# panel.net
KiCad netlist of a schematic drawn in Altium Designer
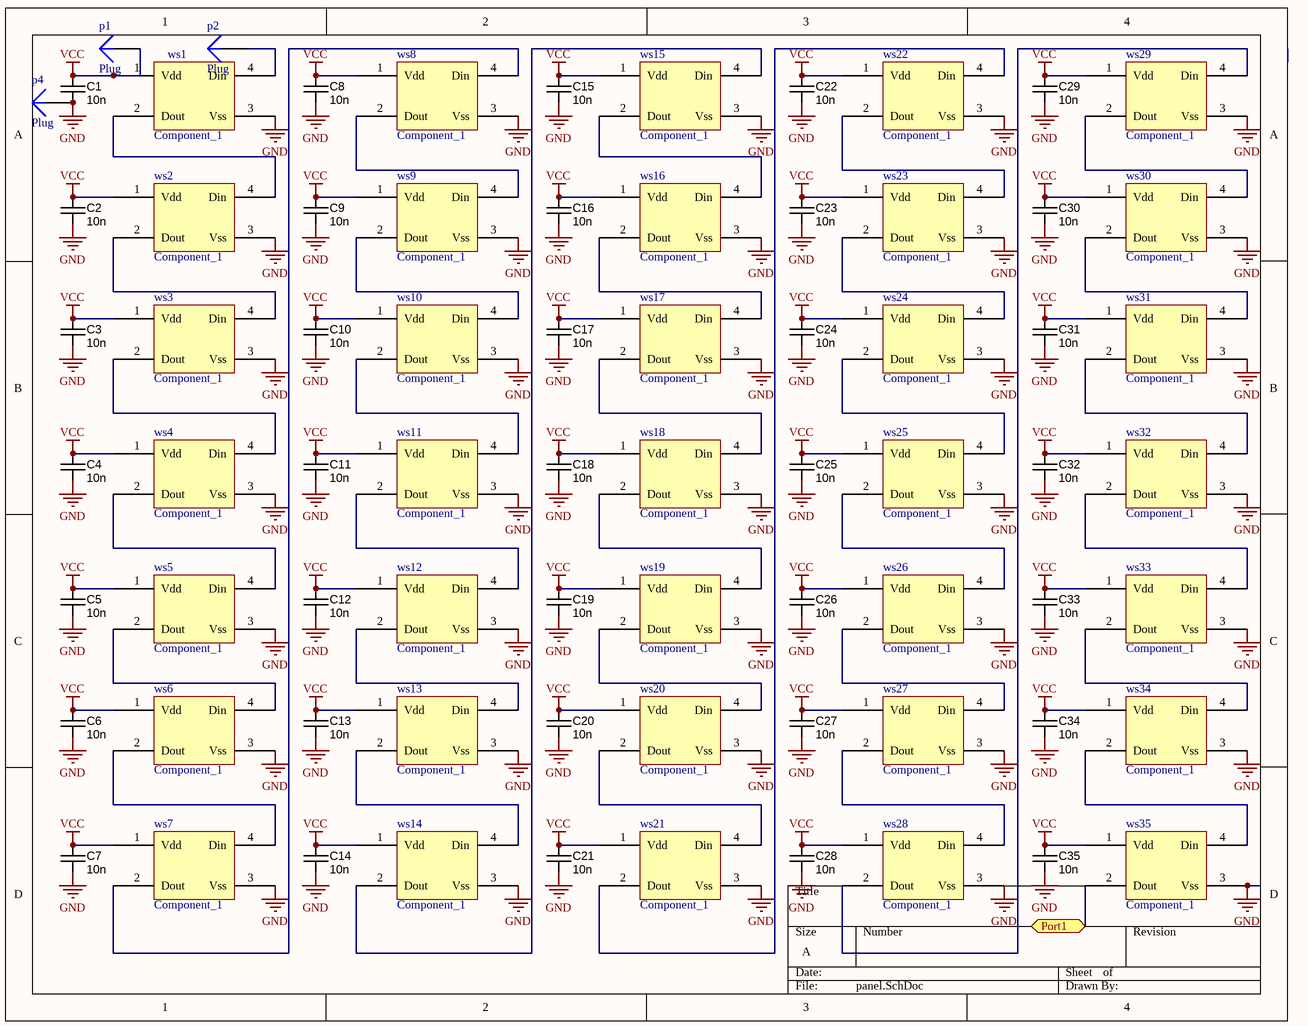
[diagram p0: panel.SchDoc]

(export (version "E")
  (design (tool "Eeschema 10.0.6"))
  (components
    (comp (ref "C1")
      (value "10n")
      (footprint "CAPC1608X90N")
      (description "Capacitor SMD Cer 10nF 10% 100V X7R 0603")
      (fields
        (field (name "TOLERANCE") "±10%")
        (field (name "MANUFACTURER") "Murata Electronics North America")
      )
      (libsource (lib "PBL - Capacitors") (part "CAPC_10n_0603_X7R_100V_10%"))
    )
    (comp (ref "C2")
      (value "10n")
      (footprint "CAPC1608X90N")
      (description "Capacitor SMD Cer 10nF 10% 100V X7R 0603")
      (fields
        (field (name "TOLERANCE") "±10%")
        (field (name "MANUFACTURER") "Murata Electronics North America")
      )
      (libsource (lib "PBL - Capacitors") (part "CAPC_10n_0603_X7R_100V_10%"))
    )
    (comp (ref "C3")
      (value "10n")
      (footprint "CAPC1608X90N")
      (description "Capacitor SMD Cer 10nF 10% 100V X7R 0603")
      (fields
        (field (name "TOLERANCE") "±10%")
        (field (name "MANUFACTURER") "Murata Electronics North America")
      )
      (libsource (lib "PBL - Capacitors") (part "CAPC_10n_0603_X7R_100V_10%"))
    )
    (comp (ref "C4")
      (value "10n")
      (footprint "CAPC1608X90N")
      (description "Capacitor SMD Cer 10nF 10% 100V X7R 0603")
      (fields
        (field (name "TOLERANCE") "±10%")
        (field (name "MANUFACTURER") "Murata Electronics North America")
      )
      (libsource (lib "PBL - Capacitors") (part "CAPC_10n_0603_X7R_100V_10%"))
    )
    (comp (ref "C5")
      (value "10n")
      (footprint "CAPC1608X90N")
      (description "Capacitor SMD Cer 10nF 10% 100V X7R 0603")
      (fields
        (field (name "TOLERANCE") "±10%")
        (field (name "MANUFACTURER") "Murata Electronics North America")
      )
      (libsource (lib "PBL - Capacitors") (part "CAPC_10n_0603_X7R_100V_10%"))
    )
    (comp (ref "C6")
      (value "10n")
      (footprint "CAPC1608X90N")
      (description "Capacitor SMD Cer 10nF 10% 100V X7R 0603")
      (fields
        (field (name "TOLERANCE") "±10%")
        (field (name "MANUFACTURER") "Murata Electronics North America")
      )
      (libsource (lib "PBL - Capacitors") (part "CAPC_10n_0603_X7R_100V_10%"))
    )
    (comp (ref "C7")
      (value "10n")
      (footprint "CAPC1608X90N")
      (description "Capacitor SMD Cer 10nF 10% 100V X7R 0603")
      (fields
        (field (name "TOLERANCE") "±10%")
        (field (name "MANUFACTURER") "Murata Electronics North America")
      )
      (libsource (lib "PBL - Capacitors") (part "CAPC_10n_0603_X7R_100V_10%"))
    )
    (comp (ref "C8")
      (value "10n")
      (footprint "CAPC1608X90N")
      (description "Capacitor SMD Cer 10nF 10% 100V X7R 0603")
      (fields
        (field (name "TOLERANCE") "±10%")
        (field (name "MANUFACTURER") "Murata Electronics North America")
      )
      (libsource (lib "PBL - Capacitors") (part "CAPC_10n_0603_X7R_100V_10%"))
    )
    (comp (ref "C9")
      (value "10n")
      (footprint "CAPC1608X90N")
      (description "Capacitor SMD Cer 10nF 10% 100V X7R 0603")
      (fields
        (field (name "TOLERANCE") "±10%")
        (field (name "MANUFACTURER") "Murata Electronics North America")
      )
      (libsource (lib "PBL - Capacitors") (part "CAPC_10n_0603_X7R_100V_10%"))
    )
    (comp (ref "C10")
      (value "10n")
      (footprint "CAPC1608X90N")
      (description "Capacitor SMD Cer 10nF 10% 100V X7R 0603")
      (fields
        (field (name "TOLERANCE") "±10%")
        (field (name "MANUFACTURER") "Murata Electronics North America")
      )
      (libsource (lib "PBL - Capacitors") (part "CAPC_10n_0603_X7R_100V_10%"))
    )
    (comp (ref "C11")
      (value "10n")
      (footprint "CAPC1608X90N")
      (description "Capacitor SMD Cer 10nF 10% 100V X7R 0603")
      (fields
        (field (name "TOLERANCE") "±10%")
        (field (name "MANUFACTURER") "Murata Electronics North America")
      )
      (libsource (lib "PBL - Capacitors") (part "CAPC_10n_0603_X7R_100V_10%"))
    )
    (comp (ref "C12")
      (value "10n")
      (footprint "CAPC1608X90N")
      (description "Capacitor SMD Cer 10nF 10% 100V X7R 0603")
      (fields
        (field (name "TOLERANCE") "±10%")
        (field (name "MANUFACTURER") "Murata Electronics North America")
      )
      (libsource (lib "PBL - Capacitors") (part "CAPC_10n_0603_X7R_100V_10%"))
    )
    (comp (ref "C13")
      (value "10n")
      (footprint "CAPC1608X90N")
      (description "Capacitor SMD Cer 10nF 10% 100V X7R 0603")
      (fields
        (field (name "TOLERANCE") "±10%")
        (field (name "MANUFACTURER") "Murata Electronics North America")
      )
      (libsource (lib "PBL - Capacitors") (part "CAPC_10n_0603_X7R_100V_10%"))
    )
    (comp (ref "C14")
      (value "10n")
      (footprint "CAPC1608X90N")
      (description "Capacitor SMD Cer 10nF 10% 100V X7R 0603")
      (fields
        (field (name "TOLERANCE") "±10%")
        (field (name "MANUFACTURER") "Murata Electronics North America")
      )
      (libsource (lib "PBL - Capacitors") (part "CAPC_10n_0603_X7R_100V_10%"))
    )
    (comp (ref "C15")
      (value "10n")
      (footprint "CAPC1608X90N")
      (description "Capacitor SMD Cer 10nF 10% 100V X7R 0603")
      (fields
        (field (name "TOLERANCE") "±10%")
        (field (name "MANUFACTURER") "Murata Electronics North America")
      )
      (libsource (lib "PBL - Capacitors") (part "CAPC_10n_0603_X7R_100V_10%"))
    )
    (comp (ref "C16")
      (value "10n")
      (footprint "CAPC1608X90N")
      (description "Capacitor SMD Cer 10nF 10% 100V X7R 0603")
      (fields
        (field (name "TOLERANCE") "±10%")
        (field (name "MANUFACTURER") "Murata Electronics North America")
      )
      (libsource (lib "PBL - Capacitors") (part "CAPC_10n_0603_X7R_100V_10%"))
    )
    (comp (ref "C17")
      (value "10n")
      (footprint "CAPC1608X90N")
      (description "Capacitor SMD Cer 10nF 10% 100V X7R 0603")
      (fields
        (field (name "TOLERANCE") "±10%")
        (field (name "MANUFACTURER") "Murata Electronics North America")
      )
      (libsource (lib "PBL - Capacitors") (part "CAPC_10n_0603_X7R_100V_10%"))
    )
    (comp (ref "C18")
      (value "10n")
      (footprint "CAPC1608X90N")
      (description "Capacitor SMD Cer 10nF 10% 100V X7R 0603")
      (fields
        (field (name "TOLERANCE") "±10%")
        (field (name "MANUFACTURER") "Murata Electronics North America")
      )
      (libsource (lib "PBL - Capacitors") (part "CAPC_10n_0603_X7R_100V_10%"))
    )
    (comp (ref "C19")
      (value "10n")
      (footprint "CAPC1608X90N")
      (description "Capacitor SMD Cer 10nF 10% 100V X7R 0603")
      (fields
        (field (name "TOLERANCE") "±10%")
        (field (name "MANUFACTURER") "Murata Electronics North America")
      )
      (libsource (lib "PBL - Capacitors") (part "CAPC_10n_0603_X7R_100V_10%"))
    )
    (comp (ref "C20")
      (value "10n")
      (footprint "CAPC1608X90N")
      (description "Capacitor SMD Cer 10nF 10% 100V X7R 0603")
      (fields
        (field (name "TOLERANCE") "±10%")
        (field (name "MANUFACTURER") "Murata Electronics North America")
      )
      (libsource (lib "PBL - Capacitors") (part "CAPC_10n_0603_X7R_100V_10%"))
    )
    (comp (ref "C21")
      (value "10n")
      (footprint "CAPC1608X90N")
      (description "Capacitor SMD Cer 10nF 10% 100V X7R 0603")
      (fields
        (field (name "TOLERANCE") "±10%")
        (field (name "MANUFACTURER") "Murata Electronics North America")
      )
      (libsource (lib "PBL - Capacitors") (part "CAPC_10n_0603_X7R_100V_10%"))
    )
    (comp (ref "C22")
      (value "10n")
      (footprint "CAPC1608X90N")
      (description "Capacitor SMD Cer 10nF 10% 100V X7R 0603")
      (fields
        (field (name "TOLERANCE") "±10%")
        (field (name "MANUFACTURER") "Murata Electronics North America")
      )
      (libsource (lib "PBL - Capacitors") (part "CAPC_10n_0603_X7R_100V_10%"))
    )
    (comp (ref "C23")
      (value "10n")
      (footprint "CAPC1608X90N")
      (description "Capacitor SMD Cer 10nF 10% 100V X7R 0603")
      (fields
        (field (name "TOLERANCE") "±10%")
        (field (name "MANUFACTURER") "Murata Electronics North America")
      )
      (libsource (lib "PBL - Capacitors") (part "CAPC_10n_0603_X7R_100V_10%"))
    )
    (comp (ref "C24")
      (value "10n")
      (footprint "CAPC1608X90N")
      (description "Capacitor SMD Cer 10nF 10% 100V X7R 0603")
      (fields
        (field (name "TOLERANCE") "±10%")
        (field (name "MANUFACTURER") "Murata Electronics North America")
      )
      (libsource (lib "PBL - Capacitors") (part "CAPC_10n_0603_X7R_100V_10%"))
    )
    (comp (ref "C25")
      (value "10n")
      (footprint "CAPC1608X90N")
      (description "Capacitor SMD Cer 10nF 10% 100V X7R 0603")
      (fields
        (field (name "TOLERANCE") "±10%")
        (field (name "MANUFACTURER") "Murata Electronics North America")
      )
      (libsource (lib "PBL - Capacitors") (part "CAPC_10n_0603_X7R_100V_10%"))
    )
    (comp (ref "C26")
      (value "10n")
      (footprint "CAPC1608X90N")
      (description "Capacitor SMD Cer 10nF 10% 100V X7R 0603")
      (fields
        (field (name "TOLERANCE") "±10%")
        (field (name "MANUFACTURER") "Murata Electronics North America")
      )
      (libsource (lib "PBL - Capacitors") (part "CAPC_10n_0603_X7R_100V_10%"))
    )
    (comp (ref "C27")
      (value "10n")
      (footprint "CAPC1608X90N")
      (description "Capacitor SMD Cer 10nF 10% 100V X7R 0603")
      (fields
        (field (name "TOLERANCE") "±10%")
        (field (name "MANUFACTURER") "Murata Electronics North America")
      )
      (libsource (lib "PBL - Capacitors") (part "CAPC_10n_0603_X7R_100V_10%"))
    )
    (comp (ref "C28")
      (value "10n")
      (footprint "CAPC1608X90N")
      (description "Capacitor SMD Cer 10nF 10% 100V X7R 0603")
      (fields
        (field (name "TOLERANCE") "±10%")
        (field (name "MANUFACTURER") "Murata Electronics North America")
      )
      (libsource (lib "PBL - Capacitors") (part "CAPC_10n_0603_X7R_100V_10%"))
    )
    (comp (ref "C29")
      (value "10n")
      (footprint "CAPC1608X90N")
      (description "Capacitor SMD Cer 10nF 10% 100V X7R 0603")
      (fields
        (field (name "TOLERANCE") "±10%")
        (field (name "MANUFACTURER") "Murata Electronics North America")
      )
      (libsource (lib "PBL - Capacitors") (part "CAPC_10n_0603_X7R_100V_10%"))
    )
    (comp (ref "C30")
      (value "10n")
      (footprint "CAPC1608X90N")
      (description "Capacitor SMD Cer 10nF 10% 100V X7R 0603")
      (fields
        (field (name "TOLERANCE") "±10%")
        (field (name "MANUFACTURER") "Murata Electronics North America")
      )
      (libsource (lib "PBL - Capacitors") (part "CAPC_10n_0603_X7R_100V_10%"))
    )
    (comp (ref "C31")
      (value "10n")
      (footprint "CAPC1608X90N")
      (description "Capacitor SMD Cer 10nF 10% 100V X7R 0603")
      (fields
        (field (name "TOLERANCE") "±10%")
        (field (name "MANUFACTURER") "Murata Electronics North America")
      )
      (libsource (lib "PBL - Capacitors") (part "CAPC_10n_0603_X7R_100V_10%"))
    )
    (comp (ref "C32")
      (value "10n")
      (footprint "CAPC1608X90N")
      (description "Capacitor SMD Cer 10nF 10% 100V X7R 0603")
      (fields
        (field (name "TOLERANCE") "±10%")
        (field (name "MANUFACTURER") "Murata Electronics North America")
      )
      (libsource (lib "PBL - Capacitors") (part "CAPC_10n_0603_X7R_100V_10%"))
    )
    (comp (ref "C33")
      (value "10n")
      (footprint "CAPC1608X90N")
      (description "Capacitor SMD Cer 10nF 10% 100V X7R 0603")
      (fields
        (field (name "TOLERANCE") "±10%")
        (field (name "MANUFACTURER") "Murata Electronics North America")
      )
      (libsource (lib "PBL - Capacitors") (part "CAPC_10n_0603_X7R_100V_10%"))
    )
    (comp (ref "C34")
      (value "10n")
      (footprint "CAPC1608X90N")
      (description "Capacitor SMD Cer 10nF 10% 100V X7R 0603")
      (fields
        (field (name "TOLERANCE") "±10%")
        (field (name "MANUFACTURER") "Murata Electronics North America")
      )
      (libsource (lib "PBL - Capacitors") (part "CAPC_10n_0603_X7R_100V_10%"))
    )
    (comp (ref "C35")
      (value "10n")
      (footprint "CAPC1608X90N")
      (description "Capacitor SMD Cer 10nF 10% 100V X7R 0603")
      (fields
        (field (name "TOLERANCE") "±10%")
        (field (name "MANUFACTURER") "Murata Electronics North America")
      )
      (libsource (lib "PBL - Capacitors") (part "CAPC_10n_0603_X7R_100V_10%"))
    )
    (comp (ref "p1")
      (value "Plug")
      (footprint "PIN1")
      (fields (field (name "PUBLISHER") "Altium Limited"))
      (libsource (lib "Miscellaneous Connectors") (part "Plug"))
    )
    (comp (ref "p2")
      (value "Plug")
      (footprint "PIN1")
      (fields (field (name "PUBLISHER") "Altium Limited"))
      (libsource (lib "Miscellaneous Connectors") (part "Plug"))
    )
    (comp (ref "p4")
      (value "Plug")
      (footprint "PIN1")
      (fields (field (name "PUBLISHER") "Altium Limited"))
      (libsource (lib "Miscellaneous Connectors") (part "Plug"))
    )
    (comp (ref "ws1")
      (value "Component_1")
      (footprint "SOP4")
      (libsource (lib "ws2812b") (part "Component_1"))
    )
    (comp (ref "ws2")
      (value "Component_1")
      (footprint "SOP4")
      (libsource (lib "ws2812b") (part "Component_1"))
    )
    (comp (ref "ws3")
      (value "Component_1")
      (footprint "SOP4")
      (libsource (lib "ws2812b") (part "Component_1"))
    )
    (comp (ref "ws4")
      (value "Component_1")
      (footprint "SOP4")
      (libsource (lib "ws2812b") (part "Component_1"))
    )
    (comp (ref "ws5")
      (value "Component_1")
      (footprint "SOP4")
      (libsource (lib "ws2812b") (part "Component_1"))
    )
    (comp (ref "ws6")
      (value "Component_1")
      (footprint "SOP4")
      (libsource (lib "ws2812b") (part "Component_1"))
    )
    (comp (ref "ws7")
      (value "Component_1")
      (footprint "SOP4")
      (libsource (lib "ws2812b") (part "Component_1"))
    )
    (comp (ref "ws8")
      (value "Component_1")
      (footprint "SOP4")
      (libsource (lib "ws2812b") (part "Component_1"))
    )
    (comp (ref "ws9")
      (value "Component_1")
      (footprint "SOP4")
      (libsource (lib "ws2812b") (part "Component_1"))
    )
    (comp (ref "ws10")
      (value "Component_1")
      (footprint "SOP4")
      (libsource (lib "ws2812b") (part "Component_1"))
    )
    (comp (ref "ws11")
      (value "Component_1")
      (footprint "SOP4")
      (libsource (lib "ws2812b") (part "Component_1"))
    )
    (comp (ref "ws12")
      (value "Component_1")
      (footprint "SOP4")
      (libsource (lib "ws2812b") (part "Component_1"))
    )
    (comp (ref "ws13")
      (value "Component_1")
      (footprint "SOP4")
      (libsource (lib "ws2812b") (part "Component_1"))
    )
    (comp (ref "ws14")
      (value "Component_1")
      (footprint "SOP4")
      (libsource (lib "ws2812b") (part "Component_1"))
    )
    (comp (ref "ws15")
      (value "Component_1")
      (footprint "SOP4")
      (libsource (lib "ws2812b") (part "Component_1"))
    )
    (comp (ref "ws16")
      (value "Component_1")
      (footprint "SOP4")
      (libsource (lib "ws2812b") (part "Component_1"))
    )
    (comp (ref "ws17")
      (value "Component_1")
      (footprint "SOP4")
      (libsource (lib "ws2812b") (part "Component_1"))
    )
    (comp (ref "ws18")
      (value "Component_1")
      (footprint "SOP4")
      (libsource (lib "ws2812b") (part "Component_1"))
    )
    (comp (ref "ws19")
      (value "Component_1")
      (footprint "SOP4")
      (libsource (lib "ws2812b") (part "Component_1"))
    )
    (comp (ref "ws20")
      (value "Component_1")
      (footprint "SOP4")
      (libsource (lib "ws2812b") (part "Component_1"))
    )
    (comp (ref "ws21")
      (value "Component_1")
      (footprint "SOP4")
      (libsource (lib "ws2812b") (part "Component_1"))
    )
    (comp (ref "ws22")
      (value "Component_1")
      (footprint "SOP4")
      (libsource (lib "ws2812b") (part "Component_1"))
    )
    (comp (ref "ws23")
      (value "Component_1")
      (footprint "SOP4")
      (libsource (lib "ws2812b") (part "Component_1"))
    )
    (comp (ref "ws24")
      (value "Component_1")
      (footprint "SOP4")
      (libsource (lib "ws2812b") (part "Component_1"))
    )
    (comp (ref "ws25")
      (value "Component_1")
      (footprint "SOP4")
      (libsource (lib "ws2812b") (part "Component_1"))
    )
    (comp (ref "ws26")
      (value "Component_1")
      (footprint "SOP4")
      (libsource (lib "ws2812b") (part "Component_1"))
    )
    (comp (ref "ws27")
      (value "Component_1")
      (footprint "SOP4")
      (libsource (lib "ws2812b") (part "Component_1"))
    )
    (comp (ref "ws28")
      (value "Component_1")
      (footprint "SOP4")
      (libsource (lib "ws2812b") (part "Component_1"))
    )
    (comp (ref "ws29")
      (value "Component_1")
      (footprint "SOP4")
      (libsource (lib "ws2812b") (part "Component_1"))
    )
    (comp (ref "ws30")
      (value "Component_1")
      (footprint "SOP4")
      (libsource (lib "ws2812b") (part "Component_1"))
    )
    (comp (ref "ws31")
      (value "Component_1")
      (footprint "SOP4")
      (libsource (lib "ws2812b") (part "Component_1"))
    )
    (comp (ref "ws32")
      (value "Component_1")
      (footprint "SOP4")
      (libsource (lib "ws2812b") (part "Component_1"))
    )
    (comp (ref "ws33")
      (value "Component_1")
      (footprint "SOP4")
      (libsource (lib "ws2812b") (part "Component_1"))
    )
    (comp (ref "ws34")
      (value "Component_1")
      (footprint "SOP4")
      (libsource (lib "ws2812b") (part "Component_1"))
    )
    (comp (ref "ws35")
      (value "Component_1")
      (footprint "SOP4")
      (libsource (lib "ws2812b") (part "Component_1"))
    )
  )
  (nets
    (net (code "1") (name "/Port1") (class "Default")
      (node (ref "ws35") (pin "2") (pinfunction "Dout_2") (pintype "passive"))
    )
    (net (code "2") (name "GND") (class "Default")
      (node (ref "C1") (pin "2") (pintype "passive"))
      (node (ref "C10") (pin "2") (pintype "passive"))
      (node (ref "C11") (pin "2") (pintype "passive"))
      (node (ref "C12") (pin "2") (pintype "passive"))
      (node (ref "C13") (pin "2") (pintype "passive"))
      (node (ref "C14") (pin "2") (pintype "passive"))
      (node (ref "C15") (pin "2") (pintype "passive"))
      (node (ref "C16") (pin "2") (pintype "passive"))
      (node (ref "C17") (pin "2") (pintype "passive"))
      (node (ref "C18") (pin "2") (pintype "passive"))
      (node (ref "C19") (pin "2") (pintype "passive"))
      (node (ref "C2") (pin "2") (pintype "passive"))
      (node (ref "C20") (pin "2") (pintype "passive"))
      (node (ref "C21") (pin "2") (pintype "passive"))
      (node (ref "C22") (pin "2") (pintype "passive"))
      (node (ref "C23") (pin "2") (pintype "passive"))
      (node (ref "C24") (pin "2") (pintype "passive"))
      (node (ref "C25") (pin "2") (pintype "passive"))
      (node (ref "C26") (pin "2") (pintype "passive"))
      (node (ref "C27") (pin "2") (pintype "passive"))
      (node (ref "C28") (pin "2") (pintype "passive"))
      (node (ref "C29") (pin "2") (pintype "passive"))
      (node (ref "C3") (pin "2") (pintype "passive"))
      (node (ref "C30") (pin "2") (pintype "passive"))
      (node (ref "C31") (pin "2") (pintype "passive"))
      (node (ref "C32") (pin "2") (pintype "passive"))
      (node (ref "C33") (pin "2") (pintype "passive"))
      (node (ref "C34") (pin "2") (pintype "passive"))
      (node (ref "C35") (pin "2") (pintype "passive"))
      (node (ref "C4") (pin "2") (pintype "passive"))
      (node (ref "C5") (pin "2") (pintype "passive"))
      (node (ref "C6") (pin "2") (pintype "passive"))
      (node (ref "C7") (pin "2") (pintype "passive"))
      (node (ref "C8") (pin "2") (pintype "passive"))
      (node (ref "C9") (pin "2") (pintype "passive"))
      (node (ref "p4") (pin "1") (pinfunction "1_1") (pintype "passive"))
      (node (ref "ws1") (pin "3") (pinfunction "Vss_3") (pintype "passive"))
      (node (ref "ws10") (pin "3") (pinfunction "Vss_3") (pintype "passive"))
      (node (ref "ws11") (pin "3") (pinfunction "Vss_3") (pintype "passive"))
      (node (ref "ws12") (pin "3") (pinfunction "Vss_3") (pintype "passive"))
      (node (ref "ws13") (pin "3") (pinfunction "Vss_3") (pintype "passive"))
      (node (ref "ws14") (pin "3") (pinfunction "Vss_3") (pintype "passive"))
      (node (ref "ws15") (pin "3") (pinfunction "Vss_3") (pintype "passive"))
      (node (ref "ws16") (pin "3") (pinfunction "Vss_3") (pintype "passive"))
      (node (ref "ws17") (pin "3") (pinfunction "Vss_3") (pintype "passive"))
      (node (ref "ws18") (pin "3") (pinfunction "Vss_3") (pintype "passive"))
      (node (ref "ws19") (pin "3") (pinfunction "Vss_3") (pintype "passive"))
      (node (ref "ws2") (pin "3") (pinfunction "Vss_3") (pintype "passive"))
      (node (ref "ws20") (pin "3") (pinfunction "Vss_3") (pintype "passive"))
      (node (ref "ws21") (pin "3") (pinfunction "Vss_3") (pintype "passive"))
      (node (ref "ws22") (pin "3") (pinfunction "Vss_3") (pintype "passive"))
      (node (ref "ws23") (pin "3") (pinfunction "Vss_3") (pintype "passive"))
      (node (ref "ws24") (pin "3") (pinfunction "Vss_3") (pintype "passive"))
      (node (ref "ws25") (pin "3") (pinfunction "Vss_3") (pintype "passive"))
      (node (ref "ws26") (pin "3") (pinfunction "Vss_3") (pintype "passive"))
      (node (ref "ws27") (pin "3") (pinfunction "Vss_3") (pintype "passive"))
      (node (ref "ws28") (pin "3") (pinfunction "Vss_3") (pintype "passive"))
      (node (ref "ws29") (pin "3") (pinfunction "Vss_3") (pintype "passive"))
      (node (ref "ws3") (pin "3") (pinfunction "Vss_3") (pintype "passive"))
      (node (ref "ws30") (pin "3") (pinfunction "Vss_3") (pintype "passive"))
      (node (ref "ws31") (pin "3") (pinfunction "Vss_3") (pintype "passive"))
      (node (ref "ws32") (pin "3") (pinfunction "Vss_3") (pintype "passive"))
      (node (ref "ws33") (pin "3") (pinfunction "Vss_3") (pintype "passive"))
      (node (ref "ws34") (pin "3") (pinfunction "Vss_3") (pintype "passive"))
      (node (ref "ws35") (pin "3") (pinfunction "Vss_3") (pintype "passive"))
      (node (ref "ws4") (pin "3") (pinfunction "Vss_3") (pintype "passive"))
      (node (ref "ws5") (pin "3") (pinfunction "Vss_3") (pintype "passive"))
      (node (ref "ws6") (pin "3") (pinfunction "Vss_3") (pintype "passive"))
      (node (ref "ws7") (pin "3") (pinfunction "Vss_3") (pintype "passive"))
      (node (ref "ws8") (pin "3") (pinfunction "Vss_3") (pintype "passive"))
      (node (ref "ws9") (pin "3") (pinfunction "Vss_3") (pintype "passive"))
    )
    (net (code "3") (name "Net-(ws1-Din)") (class "Default")
      (node (ref "p2") (pin "1") (pinfunction "1_1") (pintype "passive"))
      (node (ref "ws1") (pin "4") (pinfunction "Din_4") (pintype "passive"))
    )
    (net (code "4") (name "Net-(ws1-Dout)") (class "Default")
      (node (ref "ws1") (pin "2") (pinfunction "Dout_2") (pintype "passive"))
      (node (ref "ws2") (pin "4") (pinfunction "Din_4") (pintype "passive"))
    )
    (net (code "5") (name "Net-(ws2-Dout)") (class "Default")
      (node (ref "ws2") (pin "2") (pinfunction "Dout_2") (pintype "passive"))
      (node (ref "ws3") (pin "4") (pinfunction "Din_4") (pintype "passive"))
    )
    (net (code "6") (name "Net-(ws3-Dout)") (class "Default")
      (node (ref "ws3") (pin "2") (pinfunction "Dout_2") (pintype "passive"))
      (node (ref "ws4") (pin "4") (pinfunction "Din_4") (pintype "passive"))
    )
    (net (code "7") (name "Net-(ws4-Dout)") (class "Default")
      (node (ref "ws4") (pin "2") (pinfunction "Dout_2") (pintype "passive"))
      (node (ref "ws5") (pin "4") (pinfunction "Din_4") (pintype "passive"))
    )
    (net (code "8") (name "Net-(ws5-Dout)") (class "Default")
      (node (ref "ws5") (pin "2") (pinfunction "Dout_2") (pintype "passive"))
      (node (ref "ws6") (pin "4") (pinfunction "Din_4") (pintype "passive"))
    )
    (net (code "9") (name "Net-(ws6-Dout)") (class "Default")
      (node (ref "ws6") (pin "2") (pinfunction "Dout_2") (pintype "passive"))
      (node (ref "ws7") (pin "4") (pinfunction "Din_4") (pintype "passive"))
    )
    (net (code "10") (name "Net-(ws7-Dout)") (class "Default")
      (node (ref "ws7") (pin "2") (pinfunction "Dout_2") (pintype "passive"))
      (node (ref "ws8") (pin "4") (pinfunction "Din_4") (pintype "passive"))
    )
    (net (code "11") (name "Net-(ws8-Dout)") (class "Default")
      (node (ref "ws8") (pin "2") (pinfunction "Dout_2") (pintype "passive"))
      (node (ref "ws9") (pin "4") (pinfunction "Din_4") (pintype "passive"))
    )
    (net (code "12") (name "Net-(ws10-Din)") (class "Default")
      (node (ref "ws10") (pin "4") (pinfunction "Din_4") (pintype "passive"))
      (node (ref "ws9") (pin "2") (pinfunction "Dout_2") (pintype "passive"))
    )
    (net (code "13") (name "Net-(ws10-Dout)") (class "Default")
      (node (ref "ws10") (pin "2") (pinfunction "Dout_2") (pintype "passive"))
      (node (ref "ws11") (pin "4") (pinfunction "Din_4") (pintype "passive"))
    )
    (net (code "14") (name "Net-(ws11-Dout)") (class "Default")
      (node (ref "ws11") (pin "2") (pinfunction "Dout_2") (pintype "passive"))
      (node (ref "ws12") (pin "4") (pinfunction "Din_4") (pintype "passive"))
    )
    (net (code "15") (name "Net-(ws12-Dout)") (class "Default")
      (node (ref "ws12") (pin "2") (pinfunction "Dout_2") (pintype "passive"))
      (node (ref "ws13") (pin "4") (pinfunction "Din_4") (pintype "passive"))
    )
    (net (code "16") (name "Net-(ws13-Dout)") (class "Default")
      (node (ref "ws13") (pin "2") (pinfunction "Dout_2") (pintype "passive"))
      (node (ref "ws14") (pin "4") (pinfunction "Din_4") (pintype "passive"))
    )
    (net (code "17") (name "Net-(ws14-Dout)") (class "Default")
      (node (ref "ws14") (pin "2") (pinfunction "Dout_2") (pintype "passive"))
      (node (ref "ws15") (pin "4") (pinfunction "Din_4") (pintype "passive"))
    )
    (net (code "18") (name "Net-(ws15-Dout)") (class "Default")
      (node (ref "ws15") (pin "2") (pinfunction "Dout_2") (pintype "passive"))
      (node (ref "ws16") (pin "4") (pinfunction "Din_4") (pintype "passive"))
    )
    (net (code "19") (name "Net-(ws16-Dout)") (class "Default")
      (node (ref "ws16") (pin "2") (pinfunction "Dout_2") (pintype "passive"))
      (node (ref "ws17") (pin "4") (pinfunction "Din_4") (pintype "passive"))
    )
    (net (code "20") (name "Net-(ws17-Dout)") (class "Default")
      (node (ref "ws17") (pin "2") (pinfunction "Dout_2") (pintype "passive"))
      (node (ref "ws18") (pin "4") (pinfunction "Din_4") (pintype "passive"))
    )
    (net (code "21") (name "Net-(ws18-Dout)") (class "Default")
      (node (ref "ws18") (pin "2") (pinfunction "Dout_2") (pintype "passive"))
      (node (ref "ws19") (pin "4") (pinfunction "Din_4") (pintype "passive"))
    )
    (net (code "22") (name "Net-(ws19-Dout)") (class "Default")
      (node (ref "ws19") (pin "2") (pinfunction "Dout_2") (pintype "passive"))
      (node (ref "ws20") (pin "4") (pinfunction "Din_4") (pintype "passive"))
    )
    (net (code "23") (name "Net-(ws20-Dout)") (class "Default")
      (node (ref "ws20") (pin "2") (pinfunction "Dout_2") (pintype "passive"))
      (node (ref "ws21") (pin "4") (pinfunction "Din_4") (pintype "passive"))
    )
    (net (code "24") (name "Net-(ws21-Dout)") (class "Default")
      (node (ref "ws21") (pin "2") (pinfunction "Dout_2") (pintype "passive"))
      (node (ref "ws22") (pin "4") (pinfunction "Din_4") (pintype "passive"))
    )
    (net (code "25") (name "Net-(ws22-Dout)") (class "Default")
      (node (ref "ws22") (pin "2") (pinfunction "Dout_2") (pintype "passive"))
      (node (ref "ws23") (pin "4") (pinfunction "Din_4") (pintype "passive"))
    )
    (net (code "26") (name "Net-(ws23-Dout)") (class "Default")
      (node (ref "ws23") (pin "2") (pinfunction "Dout_2") (pintype "passive"))
      (node (ref "ws24") (pin "4") (pinfunction "Din_4") (pintype "passive"))
    )
    (net (code "27") (name "Net-(ws24-Dout)") (class "Default")
      (node (ref "ws24") (pin "2") (pinfunction "Dout_2") (pintype "passive"))
      (node (ref "ws25") (pin "4") (pinfunction "Din_4") (pintype "passive"))
    )
    (net (code "28") (name "Net-(ws25-Dout)") (class "Default")
      (node (ref "ws25") (pin "2") (pinfunction "Dout_2") (pintype "passive"))
      (node (ref "ws26") (pin "4") (pinfunction "Din_4") (pintype "passive"))
    )
    (net (code "29") (name "Net-(ws26-Dout)") (class "Default")
      (node (ref "ws26") (pin "2") (pinfunction "Dout_2") (pintype "passive"))
      (node (ref "ws27") (pin "4") (pinfunction "Din_4") (pintype "passive"))
    )
    (net (code "30") (name "Net-(ws27-Dout)") (class "Default")
      (node (ref "ws27") (pin "2") (pinfunction "Dout_2") (pintype "passive"))
      (node (ref "ws28") (pin "4") (pinfunction "Din_4") (pintype "passive"))
    )
    (net (code "31") (name "Net-(ws28-Dout)") (class "Default")
      (node (ref "ws28") (pin "2") (pinfunction "Dout_2") (pintype "passive"))
      (node (ref "ws29") (pin "4") (pinfunction "Din_4") (pintype "passive"))
    )
    (net (code "32") (name "Net-(ws29-Dout)") (class "Default")
      (node (ref "ws29") (pin "2") (pinfunction "Dout_2") (pintype "passive"))
      (node (ref "ws30") (pin "4") (pinfunction "Din_4") (pintype "passive"))
    )
    (net (code "33") (name "Net-(ws30-Dout)") (class "Default")
      (node (ref "ws30") (pin "2") (pinfunction "Dout_2") (pintype "passive"))
      (node (ref "ws31") (pin "4") (pinfunction "Din_4") (pintype "passive"))
    )
    (net (code "34") (name "Net-(ws31-Dout)") (class "Default")
      (node (ref "ws31") (pin "2") (pinfunction "Dout_2") (pintype "passive"))
      (node (ref "ws32") (pin "4") (pinfunction "Din_4") (pintype "passive"))
    )
    (net (code "35") (name "Net-(ws32-Dout)") (class "Default")
      (node (ref "ws32") (pin "2") (pinfunction "Dout_2") (pintype "passive"))
      (node (ref "ws33") (pin "4") (pinfunction "Din_4") (pintype "passive"))
    )
    (net (code "36") (name "Net-(ws33-Dout)") (class "Default")
      (node (ref "ws33") (pin "2") (pinfunction "Dout_2") (pintype "passive"))
      (node (ref "ws34") (pin "4") (pinfunction "Din_4") (pintype "passive"))
    )
    (net (code "37") (name "Net-(ws34-Dout)") (class "Default")
      (node (ref "ws34") (pin "2") (pinfunction "Dout_2") (pintype "passive"))
      (node (ref "ws35") (pin "4") (pinfunction "Din_4") (pintype "passive"))
    )
    (net (code "38") (name "VCC") (class "Default")
      (node (ref "C1") (pin "1") (pintype "passive"))
      (node (ref "C10") (pin "1") (pintype "passive"))
      (node (ref "C11") (pin "1") (pintype "passive"))
      (node (ref "C12") (pin "1") (pintype "passive"))
      (node (ref "C13") (pin "1") (pintype "passive"))
      (node (ref "C14") (pin "1") (pintype "passive"))
      (node (ref "C15") (pin "1") (pintype "passive"))
      (node (ref "C16") (pin "1") (pintype "passive"))
      (node (ref "C17") (pin "1") (pintype "passive"))
      (node (ref "C18") (pin "1") (pintype "passive"))
      (node (ref "C19") (pin "1") (pintype "passive"))
      (node (ref "C2") (pin "1") (pintype "passive"))
      (node (ref "C20") (pin "1") (pintype "passive"))
      (node (ref "C21") (pin "1") (pintype "passive"))
      (node (ref "C22") (pin "1") (pintype "passive"))
      (node (ref "C23") (pin "1") (pintype "passive"))
      (node (ref "C24") (pin "1") (pintype "passive"))
      (node (ref "C25") (pin "1") (pintype "passive"))
      (node (ref "C26") (pin "1") (pintype "passive"))
      (node (ref "C27") (pin "1") (pintype "passive"))
      (node (ref "C28") (pin "1") (pintype "passive"))
      (node (ref "C29") (pin "1") (pintype "passive"))
      (node (ref "C3") (pin "1") (pintype "passive"))
      (node (ref "C30") (pin "1") (pintype "passive"))
      (node (ref "C31") (pin "1") (pintype "passive"))
      (node (ref "C32") (pin "1") (pintype "passive"))
      (node (ref "C33") (pin "1") (pintype "passive"))
      (node (ref "C34") (pin "1") (pintype "passive"))
      (node (ref "C35") (pin "1") (pintype "passive"))
      (node (ref "C4") (pin "1") (pintype "passive"))
      (node (ref "C5") (pin "1") (pintype "passive"))
      (node (ref "C6") (pin "1") (pintype "passive"))
      (node (ref "C7") (pin "1") (pintype "passive"))
      (node (ref "C8") (pin "1") (pintype "passive"))
      (node (ref "C9") (pin "1") (pintype "passive"))
      (node (ref "p1") (pin "1") (pinfunction "1_1") (pintype "passive"))
      (node (ref "ws1") (pin "1") (pinfunction "Vdd_1") (pintype "passive"))
      (node (ref "ws10") (pin "1") (pinfunction "Vdd_1") (pintype "passive"))
      (node (ref "ws11") (pin "1") (pinfunction "Vdd_1") (pintype "passive"))
      (node (ref "ws12") (pin "1") (pinfunction "Vdd_1") (pintype "passive"))
      (node (ref "ws13") (pin "1") (pinfunction "Vdd_1") (pintype "passive"))
      (node (ref "ws14") (pin "1") (pinfunction "Vdd_1") (pintype "passive"))
      (node (ref "ws15") (pin "1") (pinfunction "Vdd_1") (pintype "passive"))
      (node (ref "ws16") (pin "1") (pinfunction "Vdd_1") (pintype "passive"))
      (node (ref "ws17") (pin "1") (pinfunction "Vdd_1") (pintype "passive"))
      (node (ref "ws18") (pin "1") (pinfunction "Vdd_1") (pintype "passive"))
      (node (ref "ws19") (pin "1") (pinfunction "Vdd_1") (pintype "passive"))
      (node (ref "ws2") (pin "1") (pinfunction "Vdd_1") (pintype "passive"))
      (node (ref "ws20") (pin "1") (pinfunction "Vdd_1") (pintype "passive"))
      (node (ref "ws21") (pin "1") (pinfunction "Vdd_1") (pintype "passive"))
      (node (ref "ws22") (pin "1") (pinfunction "Vdd_1") (pintype "passive"))
      (node (ref "ws23") (pin "1") (pinfunction "Vdd_1") (pintype "passive"))
      (node (ref "ws24") (pin "1") (pinfunction "Vdd_1") (pintype "passive"))
      (node (ref "ws25") (pin "1") (pinfunction "Vdd_1") (pintype "passive"))
      (node (ref "ws26") (pin "1") (pinfunction "Vdd_1") (pintype "passive"))
      (node (ref "ws27") (pin "1") (pinfunction "Vdd_1") (pintype "passive"))
      (node (ref "ws28") (pin "1") (pinfunction "Vdd_1") (pintype "passive"))
      (node (ref "ws29") (pin "1") (pinfunction "Vdd_1") (pintype "passive"))
      (node (ref "ws3") (pin "1") (pinfunction "Vdd_1") (pintype "passive"))
      (node (ref "ws30") (pin "1") (pinfunction "Vdd_1") (pintype "passive"))
      (node (ref "ws31") (pin "1") (pinfunction "Vdd_1") (pintype "passive"))
      (node (ref "ws32") (pin "1") (pinfunction "Vdd_1") (pintype "passive"))
      (node (ref "ws33") (pin "1") (pinfunction "Vdd_1") (pintype "passive"))
      (node (ref "ws34") (pin "1") (pinfunction "Vdd_1") (pintype "passive"))
      (node (ref "ws35") (pin "1") (pinfunction "Vdd_1") (pintype "passive"))
      (node (ref "ws4") (pin "1") (pinfunction "Vdd_1") (pintype "passive"))
      (node (ref "ws5") (pin "1") (pinfunction "Vdd_1") (pintype "passive"))
      (node (ref "ws6") (pin "1") (pinfunction "Vdd_1") (pintype "passive"))
      (node (ref "ws7") (pin "1") (pinfunction "Vdd_1") (pintype "passive"))
      (node (ref "ws8") (pin "1") (pinfunction "Vdd_1") (pintype "passive"))
      (node (ref "ws9") (pin "1") (pinfunction "Vdd_1") (pintype "passive"))
    )
  )
)
